# Nixie_Boost_Converter.net
KiCad netlist of a schematic drawn in EAGLE
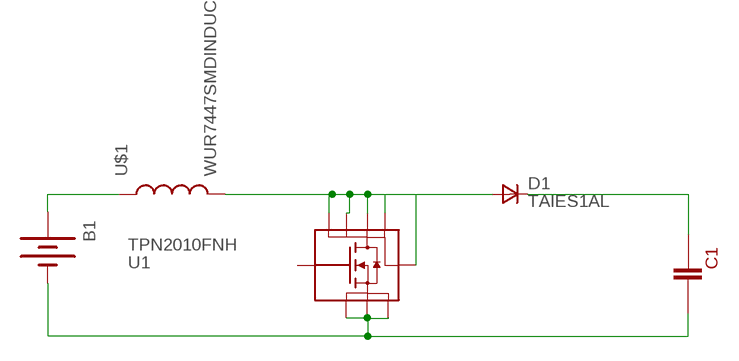
[diagram p0: schematic, sheet 1]

(export (version "E")
  (design (tool "Eeschema 10.0.6"))
  (components
    (comp (ref "B1")
      (value "2.1BARRELJACK")
      (footprint "eagle-import:2.1BARRELJACK")
      (libsource (lib "eagle-import") (part "2.1BARRELJACK"))
    )
    (comp (ref "C1")
      (value "NICHICONUUX2ECAP")
      (footprint "eagle-import:NICUUX2E")
      (libsource (lib "eagle-import") (part "NICHICONUUX2ECAP"))
    )
    (comp (ref "D1")
      (value "TAIES1AL")
      (footprint "eagle-import:TAIES1AL")
      (libsource (lib "eagle-import") (part "TAIES1AL"))
    )
    (comp (ref "U$1")
      (value "WUR7447SMDINDUCT")
      (footprint "eagle-import:WUR7447IND")
      (libsource (lib "eagle-import") (part "WUR7447SMDINDUCT"))
    )
    (comp (ref "U1")
      (value "TPN2010FNH")
      (footprint "eagle-import:TSONADVANCE")
      (libsource (lib "eagle-import") (part "TPN2010FNH"))
    )
  )
  (nets
    (net (code "1") (name "Net-(B1-GND)") (class "Default")
      (node (ref "B1") (pin "GND$1") (pinfunction "GND_GND$1") (pintype "power_in"))
      (node (ref "C1") (pin "NEG") (pinfunction "NEG_NEG") (pintype "bidirectional"))
      (node (ref "U1") (pin "S$1") (pinfunction "S$1_S$1") (pintype "passive"))
      (node (ref "U1") (pin "S$2") (pinfunction "S$2_S$2") (pintype "passive"))
      (node (ref "U1") (pin "S$3") (pinfunction "S$3_S$3") (pintype "passive"))
    )
    (net (code "2") (name "Net-(D1-A)") (class "Default")
      (node (ref "D1") (pin "A$1") (pinfunction "A_A$1") (pintype "passive"))
      (node (ref "U1") (pin "D$0") (pinfunction "D$0_D$0") (pintype "passive"))
    )
    (net (code "3") (name "Net-(D1-C)") (class "Default")
      (node (ref "C1") (pin "POS") (pinfunction "POS_POS") (pintype "bidirectional"))
      (node (ref "D1") (pin "C$1") (pinfunction "C_C$1") (pintype "passive"))
    )
    (net (code "4") (name "Net-(U$1-1)") (class "Default")
      (node (ref "B1") (pin "POS") (pinfunction "POS_POS") (pintype "power_in"))
      (node (ref "U$1") (pin "P$1") (pinfunction "1_P$1") (pintype "passive"))
    )
    (net (code "5") (name "Net-(U$1-2)") (class "Default")
      (node (ref "U$1") (pin "P$2") (pinfunction "2_P$2") (pintype "passive"))
      (node (ref "U1") (pin "D$1") (pinfunction "D$1_D$1") (pintype "passive"))
    )
    (net (code "6") (name "Net-(U1-PadD$2)") (class "Default")
      (node (ref "U1") (pin "D$2") (pinfunction "D$2_D$2") (pintype "passive"))
      (node (ref "U1") (pin "D$3") (pinfunction "D$3_D$3") (pintype "passive"))
      (node (ref "U1") (pin "D$4") (pinfunction "D$4_D$4") (pintype "passive"))
    )
    (net (code "7") (name "unconnected-(U1-PadG$1)") (class "Default")
      (node (ref "U1") (pin "G$1") (pinfunction "G$1_G$1") (pintype "passive"))
    )
  )
)
